# sym.net
KiCad netlist of a schematic drawn in EAGLE
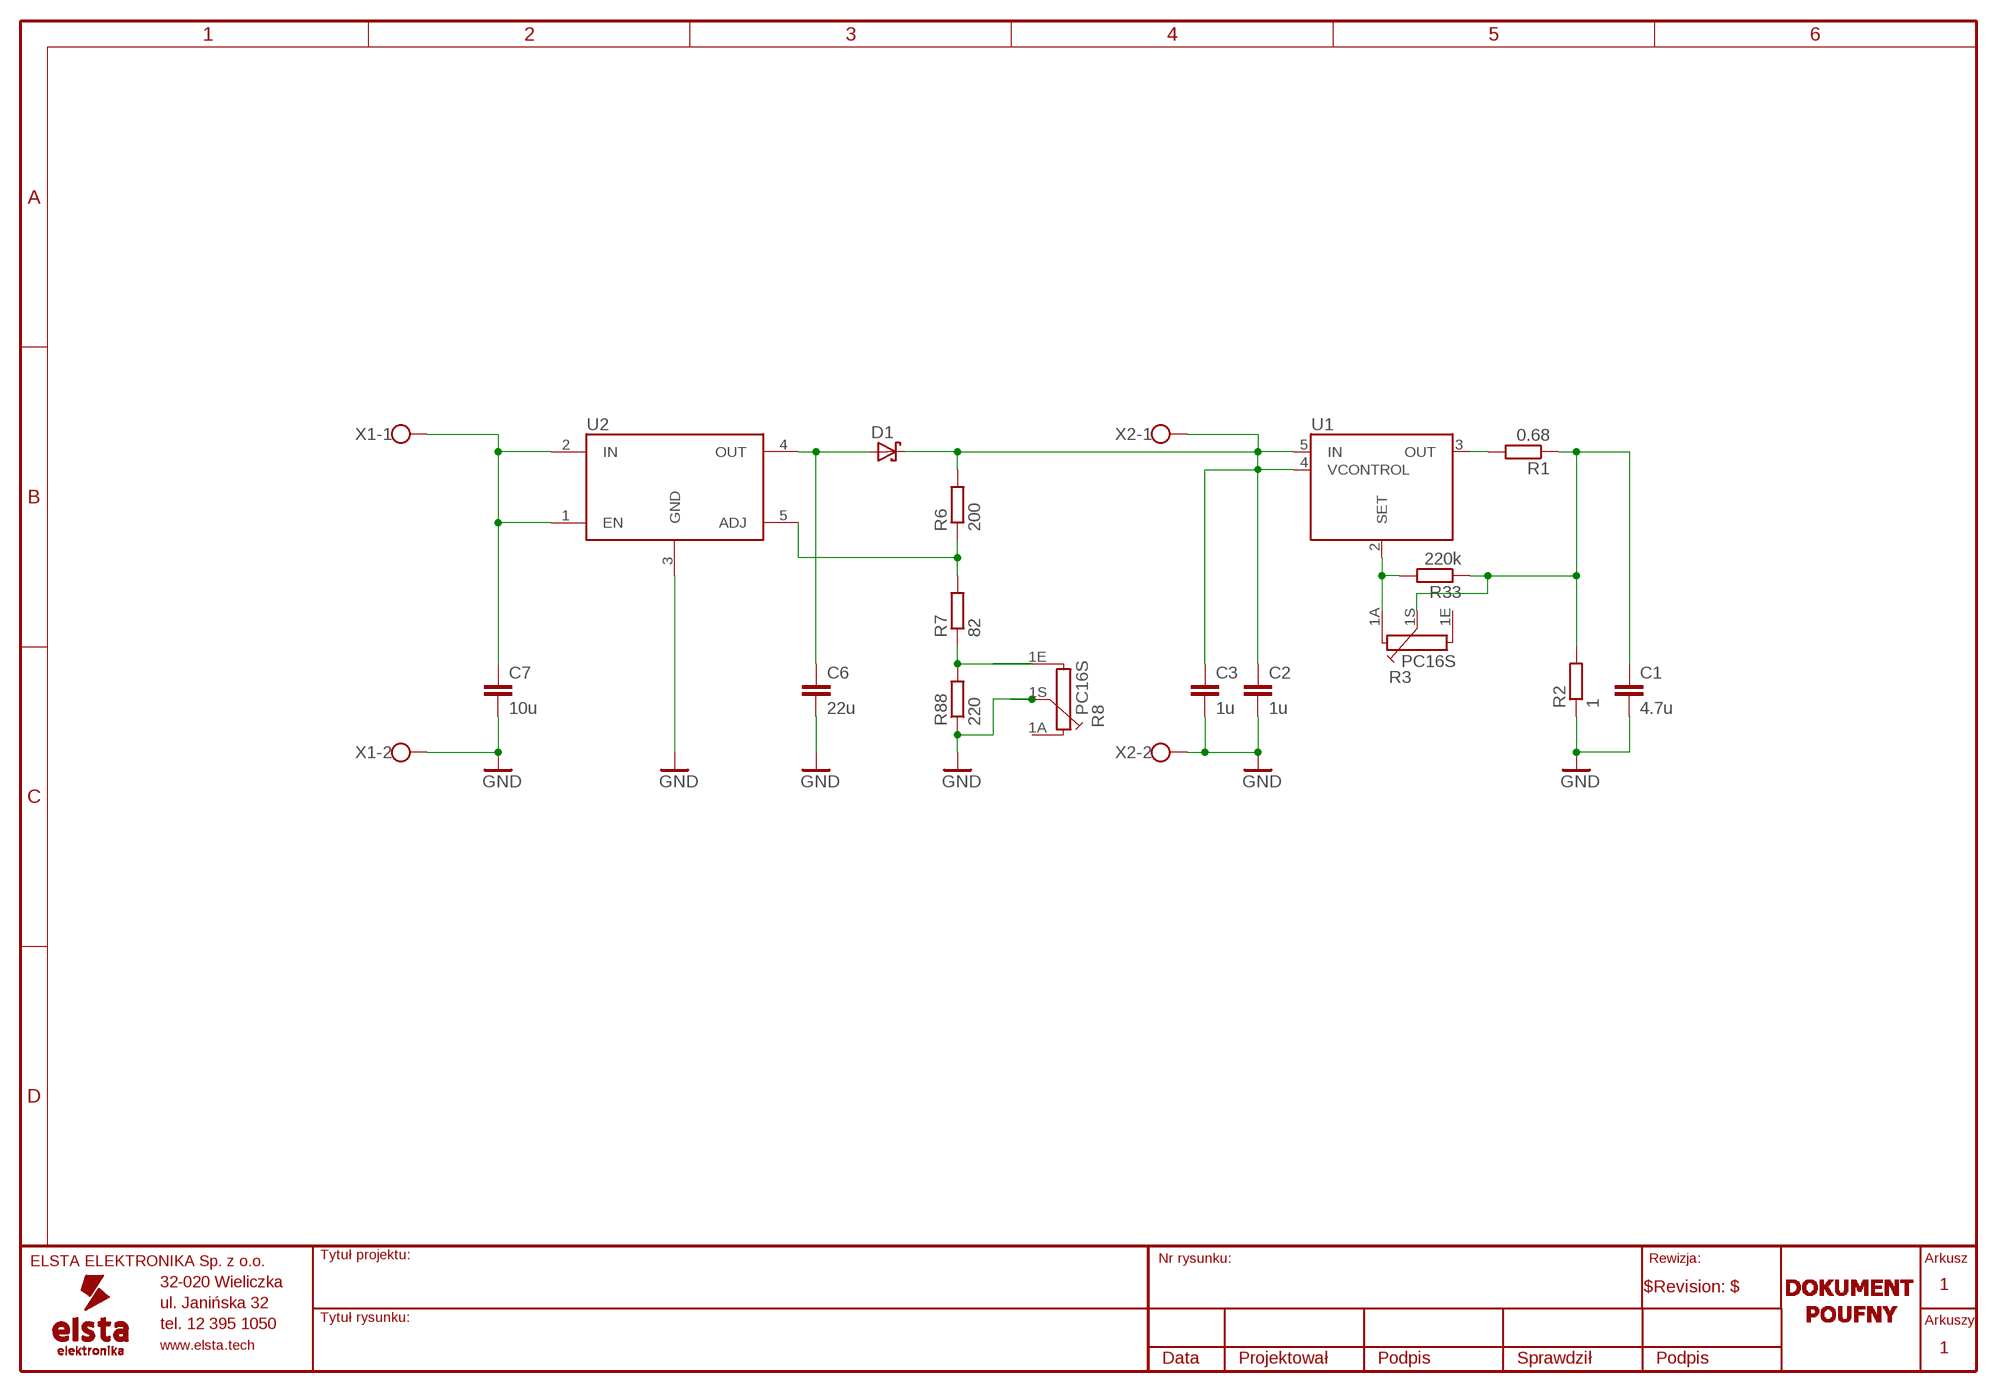
[diagram p0: schematic, sheet 1]

(export (version "E")
  (design (tool "Eeschema 10.0.6"))
  (components
    (comp (ref "C1")
      (value "4.7u")
      (footprint "eagle-import:C1206")
      (libsource (lib "eagle-import") (part "C1206"))
    )
    (comp (ref "C2")
      (value "1u")
      (footprint "eagle-import:C1206")
      (libsource (lib "eagle-import") (part "C1206"))
    )
    (comp (ref "C3")
      (value "1u")
      (footprint "eagle-import:C1206")
      (libsource (lib "eagle-import") (part "C1206"))
    )
    (comp (ref "C6")
      (value "22u")
      (footprint "eagle-import:C1206")
      (libsource (lib "eagle-import") (part "C1206"))
    )
    (comp (ref "C7")
      (value "10u")
      (footprint "eagle-import:C1206")
      (libsource (lib "eagle-import") (part "C1206"))
    )
    (comp (ref "D1")
      (value "1N5821")
      (footprint "eagle-import:D0,6")
      (libsource (lib "eagle-import") (part "1N5821"))
    )
    (comp (ref "R1")
      (value "0.68")
      (footprint "eagle-import:0617_17")
      (libsource (lib "eagle-import") (part "R-EU_0617/17"))
    )
    (comp (ref "R2")
      (value "1")
      (footprint "eagle-import:0617_17")
      (libsource (lib "eagle-import") (part "R-EU_0617/17"))
    )
    (comp (ref "R3")
      (value "PC16S")
      (footprint "eagle-import:PC16S")
      (libsource (lib "eagle-import") (part "PC16S"))
    )
    (comp (ref "R6")
      (value "200")
      (footprint "eagle-import:R1206")
      (libsource (lib "eagle-import") (part "R1206"))
    )
    (comp (ref "R7")
      (value "82")
      (footprint "eagle-import:R1206")
      (libsource (lib "eagle-import") (part "R1206"))
    )
    (comp (ref "R8")
      (value "PC16S")
      (footprint "eagle-import:PC16S")
      (libsource (lib "eagle-import") (part "PC16S"))
    )
    (comp (ref "R33")
      (value "220k")
      (footprint "eagle-import:R1206")
      (libsource (lib "eagle-import") (part "R1206"))
    )
    (comp (ref "R88")
      (value "220")
      (footprint "eagle-import:R0805")
      (libsource (lib "eagle-import") (part "R0805"))
    )
    (comp (ref "U1")
      (value "LT3080ET/IT")
      (footprint "eagle-import:TO-220-5")
      (libsource (lib "eagle-import") (part "LT3080ET/IT"))
    )
    (comp (ref "U2")
      (value "MIC29302WT")
      (footprint "eagle-import:TO-220-5")
      (libsource (lib "eagle-import") (part "MIC29302WT"))
    )
    (comp (ref "X1")
      (value "W237-02P")
      (footprint "eagle-import:W237-132")
      (libsource (lib "eagle-import") (part "W237-02P"))
    )
    (comp (ref "X2")
      (value "W237-02P")
      (footprint "eagle-import:W237-132")
      (libsource (lib "eagle-import") (part "W237-02P"))
    )
  )
  (nets
    (net (code "1") (name "GND") (class "Default")
      (node (ref "C1") (pin "2") (pinfunction "2_2") (pintype "passive"))
      (node (ref "C2") (pin "2") (pinfunction "2_2") (pintype "passive"))
      (node (ref "C3") (pin "2") (pinfunction "2_2") (pintype "passive"))
      (node (ref "C6") (pin "2") (pinfunction "2_2") (pintype "passive"))
      (node (ref "C7") (pin "2") (pinfunction "2_2") (pintype "passive"))
      (node (ref "R2") (pin "1") (pinfunction "1_1") (pintype "passive"))
      (node (ref "R8") (pin "1S") (pinfunction "1S_1S") (pintype "passive"))
      (node (ref "R88") (pin "1") (pinfunction "1_1") (pintype "passive"))
      (node (ref "U2") (pin "3") (pinfunction "GND_3") (pintype "bidirectional"))
      (node (ref "X1") (pin "2") (pinfunction "KL_2") (pintype "passive"))
      (node (ref "X2") (pin "2") (pinfunction "KL_2") (pintype "passive"))
    )
    (net (code "2") (name "Net-(C1-Pad1)") (class "Default")
      (node (ref "C1") (pin "1") (pinfunction "1_1") (pintype "passive"))
      (node (ref "R1") (pin "1") (pinfunction "1_1") (pintype "passive"))
      (node (ref "R2") (pin "2") (pinfunction "2_2") (pintype "passive"))
      (node (ref "R3") (pin "1S") (pinfunction "1S_1S") (pintype "passive"))
      (node (ref "R33") (pin "1") (pinfunction "1_1") (pintype "passive"))
    )
    (net (code "3") (name "Net-(R7-Pad1)") (class "Default")
      (node (ref "R7") (pin "1") (pinfunction "1_1") (pintype "passive"))
      (node (ref "R8") (pin "1E") (pinfunction "1E_1E") (pintype "passive"))
      (node (ref "R88") (pin "2") (pinfunction "2_2") (pintype "passive"))
    )
    (net (code "4") (name "Net-(U1-IN)") (class "Default")
      (node (ref "C2") (pin "1") (pinfunction "1_1") (pintype "passive"))
      (node (ref "C3") (pin "1") (pinfunction "1_1") (pintype "passive"))
      (node (ref "D1") (pin "C") (pinfunction "C_C") (pintype "passive"))
      (node (ref "R6") (pin "2") (pinfunction "2_2") (pintype "passive"))
      (node (ref "U1") (pin "4") (pinfunction "VCONTROL_4") (pintype "input"))
      (node (ref "U1") (pin "5") (pinfunction "IN_5") (pintype "input"))
      (node (ref "X2") (pin "1") (pinfunction "KL_1") (pintype "passive"))
    )
    (net (code "5") (name "Net-(U1-OUT)") (class "Default")
      (node (ref "R1") (pin "2") (pinfunction "2_2") (pintype "passive"))
      (node (ref "U1") (pin "3") (pinfunction "OUT_3") (pintype "output"))
    )
    (net (code "6") (name "Net-(U1-SET)") (class "Default")
      (node (ref "R3") (pin "1A") (pinfunction "1A_1A") (pintype "passive"))
      (node (ref "R33") (pin "2") (pinfunction "2_2") (pintype "passive"))
      (node (ref "U1") (pin "2") (pinfunction "SET_2") (pintype "bidirectional"))
    )
    (net (code "7") (name "Net-(U2-ADJ)") (class "Default")
      (node (ref "R6") (pin "1") (pinfunction "1_1") (pintype "passive"))
      (node (ref "R7") (pin "2") (pinfunction "2_2") (pintype "passive"))
      (node (ref "U2") (pin "5") (pinfunction "ADJ_5") (pintype "bidirectional"))
    )
    (net (code "8") (name "Net-(U2-EN)") (class "Default")
      (node (ref "C7") (pin "1") (pinfunction "1_1") (pintype "passive"))
      (node (ref "U2") (pin "1") (pinfunction "EN_1") (pintype "bidirectional"))
      (node (ref "U2") (pin "2") (pinfunction "IN_2") (pintype "bidirectional"))
      (node (ref "X1") (pin "1") (pinfunction "KL_1") (pintype "passive"))
    )
    (net (code "9") (name "Net-(U2-OUT)") (class "Default")
      (node (ref "C6") (pin "1") (pinfunction "1_1") (pintype "passive"))
      (node (ref "D1") (pin "A") (pinfunction "A_A") (pintype "passive"))
      (node (ref "U2") (pin "4") (pinfunction "OUT_4") (pintype "bidirectional"))
    )
    (net (code "10") (name "unconnected-(R3-Pad1E)") (class "Default")
      (node (ref "R3") (pin "1E") (pinfunction "1E_1E") (pintype "passive"))
    )
    (net (code "11") (name "unconnected-(R8-Pad1A)") (class "Default")
      (node (ref "R8") (pin "1A") (pinfunction "1A_1A") (pintype "passive"))
    )
  )
)
